# FPGA-m3pi.net
KiCad netlist of a schematic drawn in EAGLE
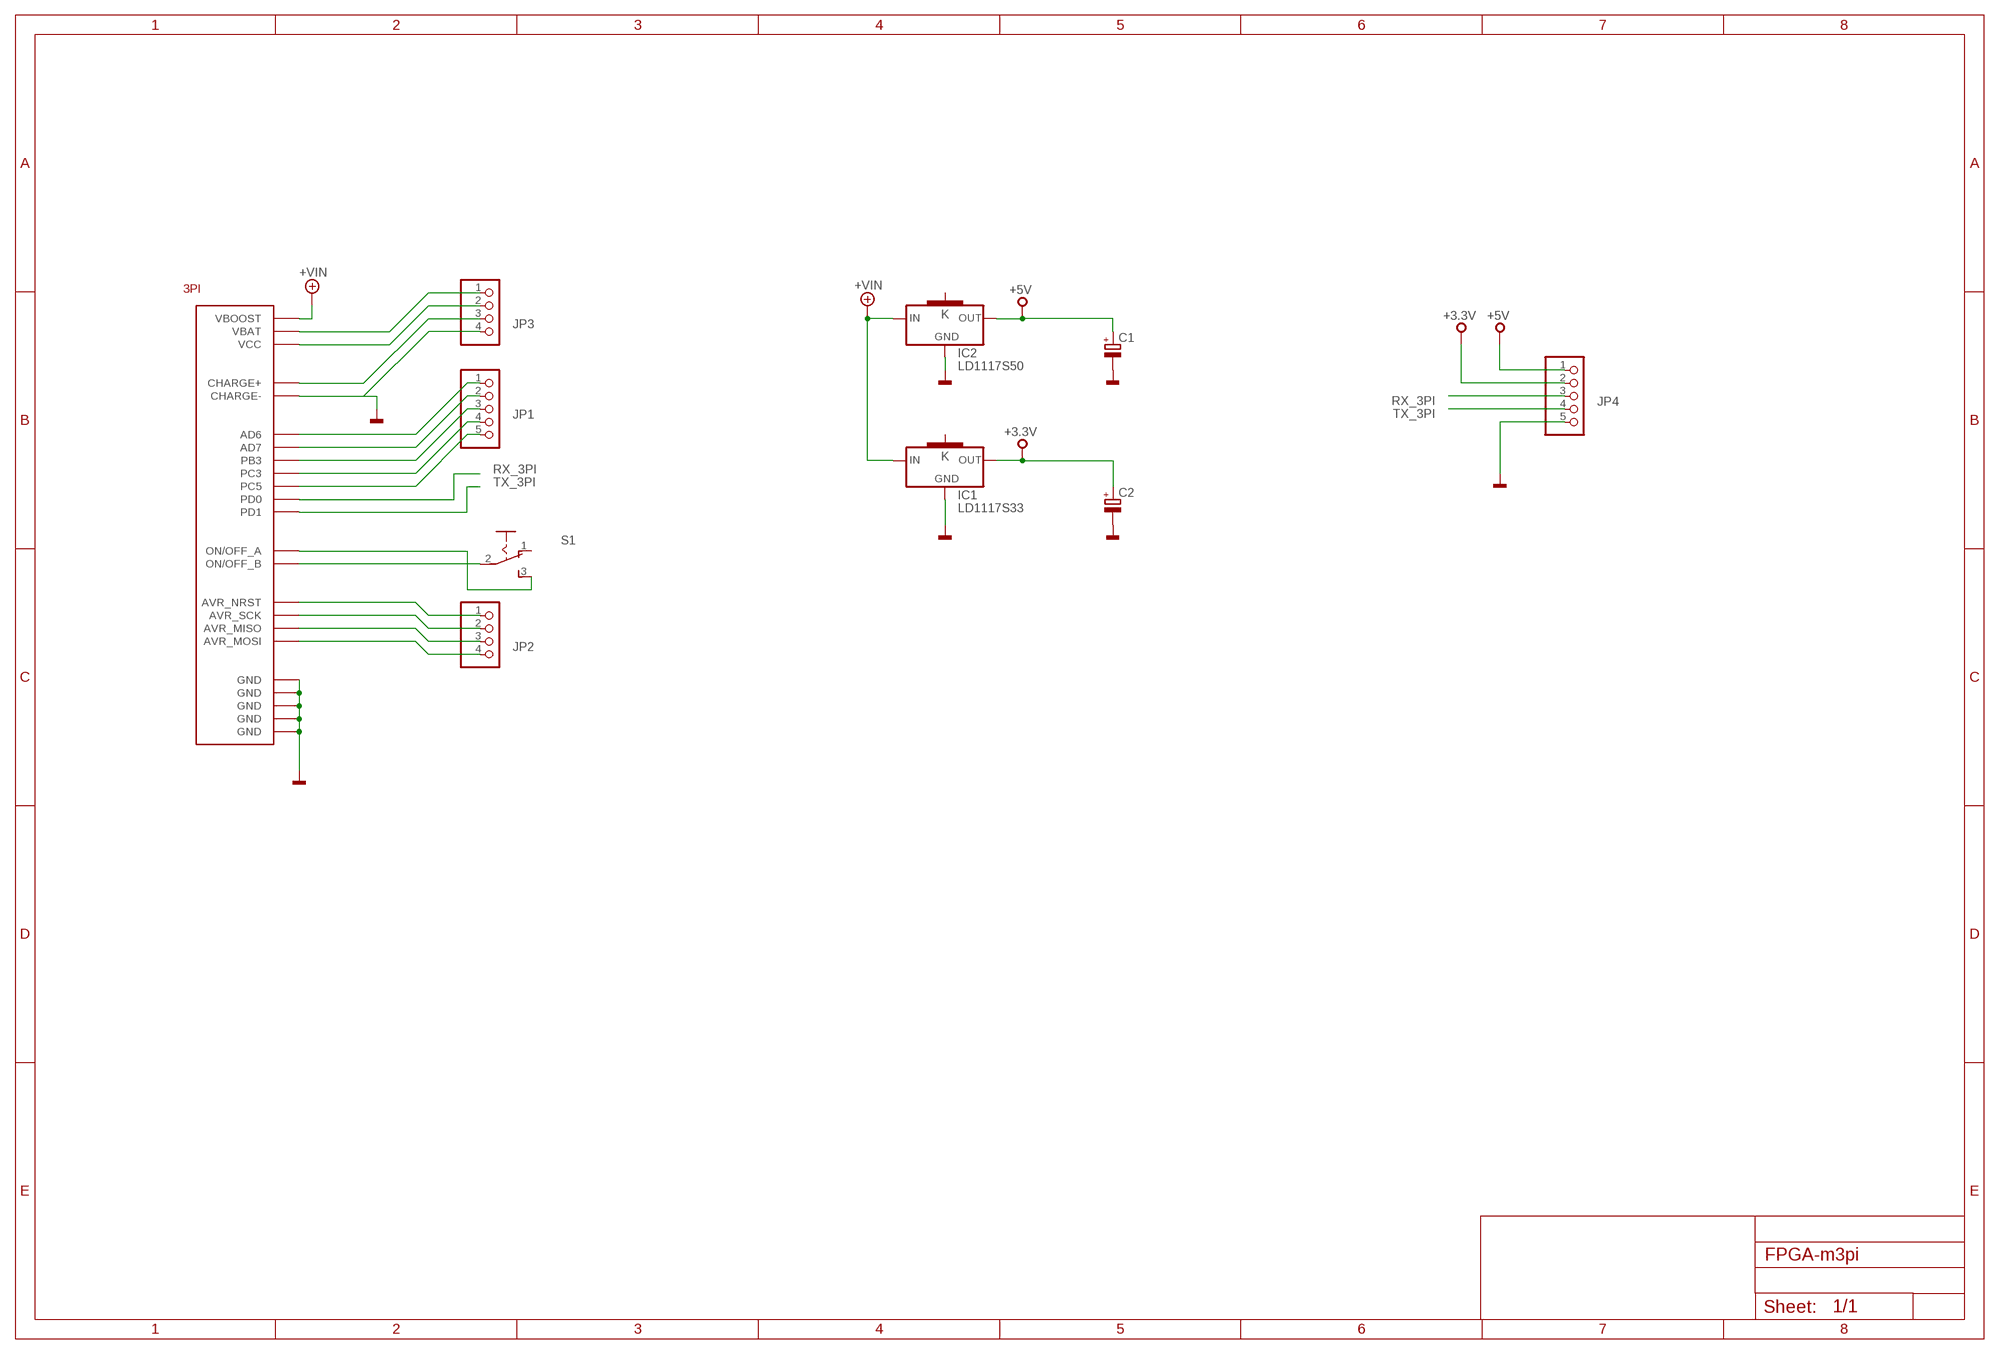
[diagram p0: schematic, sheet 1]

(export (version "E")
  (design (tool "Eeschema 10.0.6"))
  (components
    (comp (ref "C1")
      (value "CPOL-EUE2.5-5")
      (footprint "eagle-import:E2,5-5")
      (libsource (lib "eagle-import") (part "CPOL-EUE2.5-5"))
    )
    (comp (ref "C2")
      (value "CPOL-EUE2.5-5")
      (footprint "eagle-import:E2,5-5")
      (libsource (lib "eagle-import") (part "CPOL-EUE2.5-5"))
    )
    (comp (ref "IC1")
      (value "LD1117S33")
      (footprint "eagle-import:SOT223")
      (libsource (lib "eagle-import") (part "LD1117S33"))
    )
    (comp (ref "IC2")
      (value "LD1117S50")
      (footprint "eagle-import:SOT223")
      (libsource (lib "eagle-import") (part "LD1117S50"))
    )
    (comp (ref "JP1")
      (value "PINHD-1X5")
      (footprint "eagle-import:1X05")
      (libsource (lib "eagle-import") (part "PINHD-1X5"))
    )
    (comp (ref "JP2")
      (value "PINHD-1X4")
      (footprint "eagle-import:1X04")
      (libsource (lib "eagle-import") (part "PINHD-1X4"))
    )
    (comp (ref "JP3")
      (value "PINHD-1X4")
      (footprint "eagle-import:1X04")
      (libsource (lib "eagle-import") (part "PINHD-1X4"))
    )
    (comp (ref "JP4")
      (value "PINHD-1X5")
      (footprint "eagle-import:1X05")
      (libsource (lib "eagle-import") (part "PINHD-1X5"))
    )
    (comp (ref "S1")
      (value "M251")
      (footprint "eagle-import:M251")
      (libsource (lib "eagle-import") (part "M251"))
    )
    (comp (ref "U$1")
      (value "MBED-M3PI_3PI")
      (footprint "eagle-import:MBED-M3PI_3PI")
      (libsource (lib "eagle-import") (part "MBED-M3PI_3PI"))
    )
  )
  (nets
    (net (code "1") (name "+3.3V") (class "Default")
      (node (ref "C2") (pin "+") (pinfunction "+_+") (pintype "passive"))
      (node (ref "IC1") (pin "2") (pinfunction "OUT_2") (pintype "passive"))
      (node (ref "JP4") (pin "2") (pinfunction "2_2") (pintype "passive"))
    )
    (net (code "2") (name "+5V") (class "Default")
      (node (ref "C1") (pin "+") (pinfunction "+_+") (pintype "passive"))
      (node (ref "IC2") (pin "2") (pinfunction "OUT_2") (pintype "passive"))
      (node (ref "JP4") (pin "1") (pinfunction "1_1") (pintype "passive"))
    )
    (net (code "3") (name "+VIN") (class "Default")
      (node (ref "IC1") (pin "3") (pinfunction "IN_3") (pintype "input"))
      (node (ref "IC2") (pin "3") (pinfunction "IN_3") (pintype "input"))
      (node (ref "U$1") (pin "VBOOST") (pinfunction "VBOOST_VBOOST") (pintype "bidirectional"))
    )
    (net (code "4") (name "/RX_3PI") (class "Default")
      (node (ref "JP4") (pin "3") (pinfunction "3_3") (pintype "passive"))
      (node (ref "U$1") (pin "PD0") (pinfunction "PD0_PD0") (pintype "bidirectional"))
    )
    (net (code "5") (name "/TX_3PI") (class "Default")
      (node (ref "JP4") (pin "4") (pinfunction "4_4") (pintype "passive"))
      (node (ref "U$1") (pin "PD1") (pinfunction "PD1_PD1") (pintype "bidirectional"))
    )
    (net (code "6") (name "GND") (class "Default")
      (node (ref "C1") (pin "-") (pinfunction "-_-") (pintype "passive"))
      (node (ref "C2") (pin "-") (pinfunction "-_-") (pintype "passive"))
      (node (ref "IC1") (pin "1") (pinfunction "GND_1") (pintype "input"))
      (node (ref "IC2") (pin "1") (pinfunction "GND_1") (pintype "input"))
      (node (ref "JP3") (pin "4") (pinfunction "4_4") (pintype "passive"))
      (node (ref "JP4") (pin "5") (pinfunction "5_5") (pintype "passive"))
      (node (ref "U$1") (pin "CHARGE-") (pinfunction "CHARGE-_CHARGE-") (pintype "power_in"))
      (node (ref "U$1") (pin "GND@1") (pinfunction "GND_GND@1") (pintype "bidirectional"))
      (node (ref "U$1") (pin "GND@2") (pinfunction "GND_GND@2") (pintype "bidirectional"))
      (node (ref "U$1") (pin "GND@3") (pinfunction "GND_GND@3") (pintype "bidirectional"))
      (node (ref "U$1") (pin "GND@4") (pinfunction "GND_GND@4") (pintype "bidirectional"))
      (node (ref "U$1") (pin "GND@5") (pinfunction "GND_GND@5") (pintype "bidirectional"))
    )
    (net (code "7") (name "Net-(JP1-Pad1)") (class "Default")
      (node (ref "JP1") (pin "1") (pinfunction "1_1") (pintype "passive"))
      (node (ref "U$1") (pin "AD6") (pinfunction "AD6_AD6") (pintype "bidirectional"))
    )
    (net (code "8") (name "Net-(JP1-Pad2)") (class "Default")
      (node (ref "JP1") (pin "2") (pinfunction "2_2") (pintype "passive"))
      (node (ref "U$1") (pin "AD7") (pinfunction "AD7_AD7") (pintype "bidirectional"))
    )
    (net (code "9") (name "Net-(JP1-Pad3)") (class "Default")
      (node (ref "JP1") (pin "3") (pinfunction "3_3") (pintype "passive"))
      (node (ref "U$1") (pin "PB3") (pinfunction "PB3_PB3") (pintype "bidirectional"))
    )
    (net (code "10") (name "Net-(JP1-Pad4)") (class "Default")
      (node (ref "JP1") (pin "4") (pinfunction "4_4") (pintype "passive"))
      (node (ref "U$1") (pin "PC3") (pinfunction "PC3_PC3") (pintype "bidirectional"))
    )
    (net (code "11") (name "Net-(JP1-Pad5)") (class "Default")
      (node (ref "JP1") (pin "5") (pinfunction "5_5") (pintype "passive"))
      (node (ref "U$1") (pin "PC5") (pinfunction "PC5_PC5") (pintype "bidirectional"))
    )
    (net (code "12") (name "Net-(JP2-Pad1)") (class "Default")
      (node (ref "JP2") (pin "1") (pinfunction "1_1") (pintype "passive"))
      (node (ref "U$1") (pin "AVR_NRST") (pinfunction "AVR_NRST_AVR_NRST") (pintype "bidirectional"))
    )
    (net (code "13") (name "Net-(JP2-Pad2)") (class "Default")
      (node (ref "JP2") (pin "2") (pinfunction "2_2") (pintype "passive"))
      (node (ref "U$1") (pin "AVR_SCK") (pinfunction "AVR_SCK_AVR_SCK") (pintype "bidirectional"))
    )
    (net (code "14") (name "Net-(JP2-Pad3)") (class "Default")
      (node (ref "JP2") (pin "3") (pinfunction "3_3") (pintype "passive"))
      (node (ref "U$1") (pin "AVR_MISO") (pinfunction "AVR_MISO_AVR_MISO") (pintype "bidirectional"))
    )
    (net (code "15") (name "Net-(JP2-Pad4)") (class "Default")
      (node (ref "JP2") (pin "4") (pinfunction "4_4") (pintype "passive"))
      (node (ref "U$1") (pin "AVR_MOSI") (pinfunction "AVR_MOSI_AVR_MOSI") (pintype "bidirectional"))
    )
    (net (code "16") (name "Net-(JP3-Pad1)") (class "Default")
      (node (ref "JP3") (pin "1") (pinfunction "1_1") (pintype "passive"))
      (node (ref "U$1") (pin "VBAT") (pinfunction "VBAT_VBAT") (pintype "bidirectional"))
    )
    (net (code "17") (name "Net-(JP3-Pad2)") (class "Default")
      (node (ref "JP3") (pin "2") (pinfunction "2_2") (pintype "passive"))
      (node (ref "U$1") (pin "VCC") (pinfunction "VCC_VCC") (pintype "bidirectional"))
    )
    (net (code "18") (name "Net-(JP3-Pad3)") (class "Default")
      (node (ref "JP3") (pin "3") (pinfunction "3_3") (pintype "passive"))
      (node (ref "U$1") (pin "CHARGE+") (pinfunction "CHARGE+_CHARGE+") (pintype "power_in"))
    )
    (net (code "19") (name "Net-(S1-P)") (class "Default")
      (node (ref "S1") (pin "2") (pinfunction "P_2") (pintype "passive"))
      (node (ref "U$1") (pin "ON/OFF_B") (pinfunction "ON/OFF_B_ON/OFF_B") (pintype "bidirectional"))
    )
    (net (code "20") (name "Net-(S1-S)") (class "Default")
      (node (ref "S1") (pin "3") (pinfunction "S_3") (pintype "passive"))
      (node (ref "U$1") (pin "ON/OFF_A") (pinfunction "ON/OFF_A_ON/OFF_A") (pintype "bidirectional"))
    )
    (net (code "21") (name "unconnected-(IC1-K-Pad4)") (class "Default")
      (node (ref "IC1") (pin "4") (pinfunction "K_4") (pintype "passive"))
    )
    (net (code "22") (name "unconnected-(IC2-K-Pad4)") (class "Default")
      (node (ref "IC2") (pin "4") (pinfunction "K_4") (pintype "passive"))
    )
    (net (code "23") (name "unconnected-(S1-O-Pad1)") (class "Default")
      (node (ref "S1") (pin "1") (pinfunction "O_1") (pintype "passive"))
    )
  )
)
